# PR9025_A.net
KiCad netlist of a schematic drawn in EAGLE
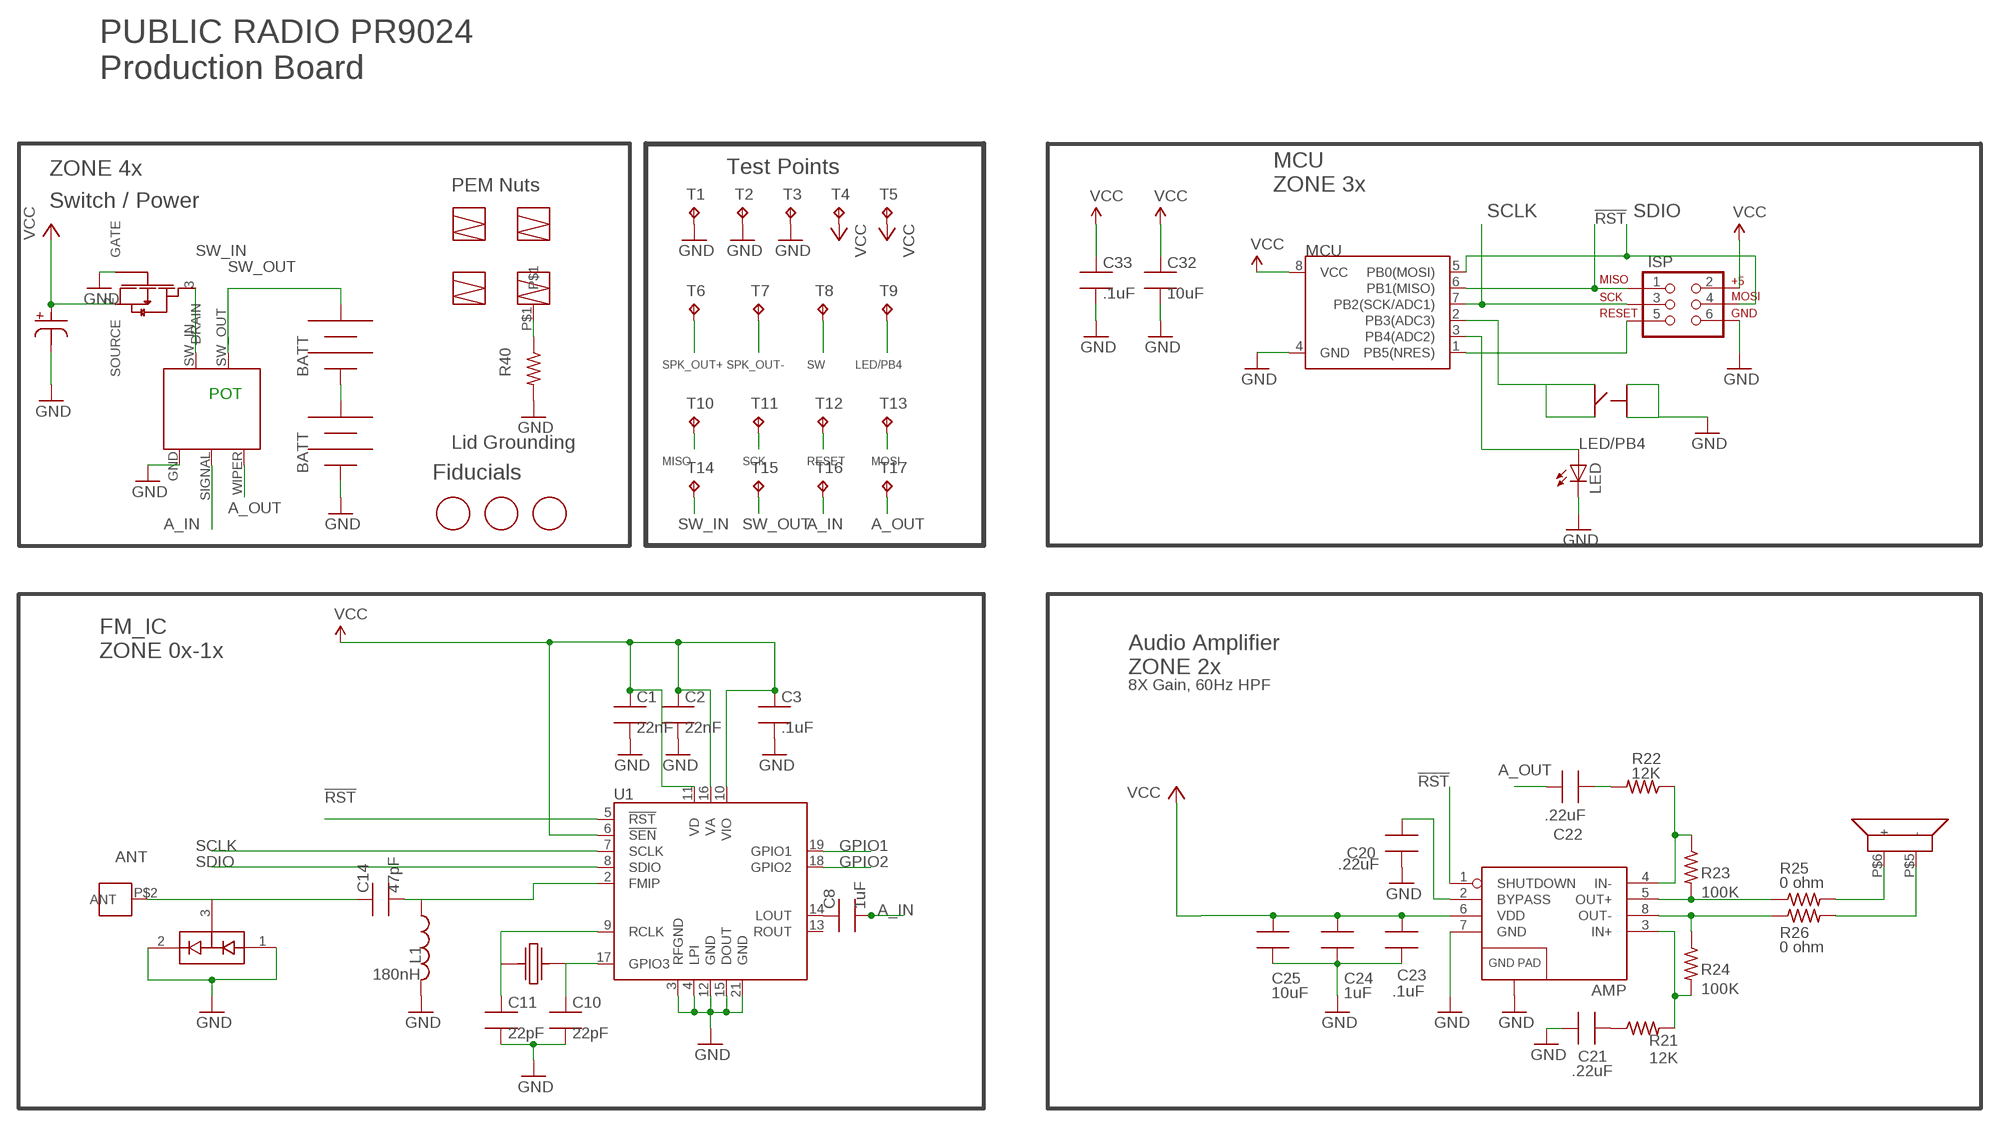
[diagram p0: schematic, sheet 1]

(export (version "E")
  (design (tool "Eeschema 10.0.6"))
  (components
    (comp (ref "AMP")
      (value "TPA6203A1")
      (footprint "eagle-import:8-MSOP")
      (libsource (lib "eagle-import") (part "TPA6203A1"))
    )
    (comp (ref "ANT_MOUNT")
      (value "DNP")
      (footprint "eagle-import:PEM_M3")
      (libsource (lib "eagle-import") (part "M3_PEMNUT"))
    )
    (comp (ref "C1")
      (value "22nF")
      (footprint "eagle-import:0603_CPL")
      (fields
        (field (name "MFG_PN") "CL10B223KB8NNNC")
        (field (name "TOL") "10%")
        (field (name "VOLTAGE") "16V")
      )
      (libsource (lib "eagle-import") (part "C_SMT_0603_CPL"))
    )
    (comp (ref "C2")
      (value "22nF")
      (footprint "eagle-import:0603_CPL")
      (fields
        (field (name "MFG_PN") "CL10B223KB8NNNC")
        (field (name "TOL") "10%")
        (field (name "VOLTAGE") "16V")
      )
      (libsource (lib "eagle-import") (part "C_SMT_0603_CPL"))
    )
    (comp (ref "C3")
      (value ".1uF")
      (footprint "eagle-import:0603_CPL")
      (fields
        (field (name "MFG_PN") "CL10B104KB8SFNC")
        (field (name "TOL") "10%")
        (field (name "VOLTAGE") "16V")
      )
      (libsource (lib "eagle-import") (part "C_SMT_0603_CPL"))
    )
    (comp (ref "C8")
      (value "1uF")
      (footprint "eagle-import:0603_CPL")
      (fields
        (field (name "MFG_PN") "CL10B105KP8NNNC")
        (field (name "TOL") "10%")
        (field (name "VOLTAGE") "10V")
      )
      (libsource (lib "eagle-import") (part "C_SMT_0603_CPL"))
    )
    (comp (ref "C10")
      (value "22pF")
      (footprint "eagle-import:0603_CPL")
      (fields
        (field (name "MFG_PN") "C1608C0G1H220J080AA")
        (field (name "TOL") "5%")
        (field (name "VOLTAGE") "50V")
      )
      (libsource (lib "eagle-import") (part "C_SMT_0603_CPL"))
    )
    (comp (ref "C11")
      (value "22pF")
      (footprint "eagle-import:0603_CPL")
      (fields
        (field (name "MFG_PN") "C1608C0G1H220J080AA")
        (field (name "TOL") "5%")
        (field (name "VOLTAGE") "50V")
      )
      (libsource (lib "eagle-import") (part "C_SMT_0603_CPL"))
    )
    (comp (ref "C14")
      (value "47pF")
      (footprint "eagle-import:0603_CPL")
      (fields
        (field (name "MFG_PN") "CL10C470JB8NCNC")
        (field (name "TOL") "5%")
        (field (name "VOLTAGE") "50V")
      )
      (libsource (lib "eagle-import") (part "C_SMT_0603_CPL"))
    )
    (comp (ref "C20")
      (value ".22uF")
      (footprint "eagle-import:0603_CPL")
      (fields
        (field (name "MFG_PN") "C1608X7R1C224K080AC")
        (field (name "TOL") "10%")
        (field (name "VOLTAGE") "16V")
      )
      (libsource (lib "eagle-import") (part "C_SMT_0603_CPL"))
    )
    (comp (ref "C21")
      (value ".22uF")
      (footprint "eagle-import:0603_CPL")
      (fields
        (field (name "MFG_PN") "C1608X7R1C224K080AC")
        (field (name "TOL") "10%")
        (field (name "VOLTAGE") "16V")
      )
      (libsource (lib "eagle-import") (part "C_SMT_0603_CPL"))
    )
    (comp (ref "C22")
      (value ".22uF")
      (footprint "eagle-import:0603_CPL")
      (fields
        (field (name "MFG_PN") "C1608X7R1C224K080AC")
        (field (name "TOL") "10%")
        (field (name "VOLTAGE") "16V")
      )
      (libsource (lib "eagle-import") (part "C_SMT_0603_CPL"))
    )
    (comp (ref "C23")
      (value ".1uF")
      (footprint "eagle-import:0603_CPL")
      (fields
        (field (name "MFG_PN") "CL10B104KB8SFNC")
        (field (name "TOL") "10%")
        (field (name "VOLTAGE") "16V")
      )
      (libsource (lib "eagle-import") (part "C_SMT_0603_CPL"))
    )
    (comp (ref "C24")
      (value "1uF")
      (footprint "eagle-import:0603_CPL")
      (fields
        (field (name "MFG_PN") "CL10B105KP8NNNC")
        (field (name "TOL") "10%")
        (field (name "VOLTAGE") "10V")
      )
      (libsource (lib "eagle-import") (part "C_SMT_0603_CPL"))
    )
    (comp (ref "C25")
      (value "10uF")
      (footprint "eagle-import:0603_CPL")
      (fields
        (field (name "MFG_PN") "CL10A106MQ8NNNC")
        (field (name "TOL") "20%")
        (field (name "VOLTAGE") "6.3V")
      )
      (libsource (lib "eagle-import") (part "C_SMT_0603_CPL"))
    )
    (comp (ref "C32")
      (value "10uF")
      (footprint "eagle-import:0603_CPL")
      (fields
        (field (name "MFG_PN") "CL10A106MQ8NNNC")
        (field (name "TOL") "20%")
        (field (name "VOLTAGE") "6.3V")
      )
      (libsource (lib "eagle-import") (part "C_SMT_0603_CPL"))
    )
    (comp (ref "C33")
      (value ".1uF")
      (footprint "eagle-import:0603_CPL")
      (fields
        (field (name "MFG_PN") "CL10B104KB8SFNC")
        (field (name "TOL") "10%")
        (field (name "VOLTAGE") "16V")
      )
      (libsource (lib "eagle-import") (part "C_SMT_0603_CPL"))
    )
    (comp (ref "C40")
      (value "220uF")
      (footprint "eagle-import:NICHICON_UD_63")
      (fields (field (name "TOL") "20%") (field (name "VOLTAGE") "16V"))
      (libsource (lib "eagle-import") (part "NICHICON_SERIESUD"))
    )
    (comp (ref "D1")
      (value "BAV99")
      (footprint "eagle-import:SOT23_CPL")
      (fields (field (name "MFG_PN") "BAV99,215"))
      (libsource (lib "eagle-import") (part "BAV99"))
    )
    (comp (ref "FET1")
      (value "AO3435")
      (footprint "eagle-import:SOT23_CPL")
      (fields (field (name "MFG_PN") "AO3435"))
      (libsource (lib "eagle-import") (part "AO3435"))
    )
    (comp (ref "ISP")
      (value "AVR_SPI_PRG_6NS")
      (footprint "eagle-import:2X3-NS")
      (libsource (lib "eagle-import") (part "AVR_SPI_PRG_6NS"))
    )
    (comp (ref "JP5")
      (value "BK-92_MPD_AA_BATT_CLIP")
      (footprint "eagle-import:BK92_AA_BATT")
      (fields (field (name "MFG_PN") "2 of BK92 - supplied by CL Labs"))
      (libsource (lib "eagle-import") (part "BK-92_MPD_AA_BATT_CLIP"))
    )
    (comp (ref "JP6")
      (value "BK-92_MPD_AA_BATT_CLIP")
      (footprint "eagle-import:BK92_AA_BATT")
      (fields (field (name "MFG_PN") "2 of BK92 - supplied by CL Labs"))
      (libsource (lib "eagle-import") (part "BK-92_MPD_AA_BATT_CLIP"))
    )
    (comp (ref "L1")
      (value "180nH")
      (footprint "eagle-import:0805_ADAFRUIT")
      (fields
        (field (name "CURRENT") "400mA")
        (field (name "DCR") "640m")
        (field (name "MFG_PN") "AISC-0805-R18J-T")
        (field (name "TOL") "5%")
      )
      (libsource (lib "eagle-import") (part "L_SMT_0805_ADAFRUIT"))
    )
    (comp (ref "LED")
      (value "HSMC-C265_REVERSE_MOUNT_LED")
      (footprint "eagle-import:HSMC-C265_REVERSE_MOUN_LED")
      (libsource (lib "eagle-import") (part "HSMC-C265_REVERSE_MOUNT_LED"))
    )
    (comp (ref "MARK1")
      (value "FIDUCIAL")
      (footprint "eagle-import:FIDUCIAL_1MM")
      (libsource (lib "eagle-import") (part "FIDUCIAL"))
    )
    (comp (ref "MARK2")
      (value "FIDUCIAL")
      (footprint "eagle-import:FIDUCIAL_1MM")
      (libsource (lib "eagle-import") (part "FIDUCIAL"))
    )
    (comp (ref "MARK3")
      (value "FIDUCIAL")
      (footprint "eagle-import:FIDUCIAL_1MM")
      (libsource (lib "eagle-import") (part "FIDUCIAL"))
    )
    (comp (ref "MCU")
      (value "ATTINY45TINY45-20-SMT")
      (footprint "eagle-import:8-SOIC")
      (libsource (lib "eagle-import") (part "ATTINY45TINY45-20-SMT"))
    )
    (comp (ref "R1")
      (value "VOLUME_POT")
      (footprint "eagle-import:H17112NS_A10K_L20F-002")
      (libsource (lib "eagle-import") (part "VOLUME_POT"))
    )
    (comp (ref "R21")
      (value "12K")
      (footprint "eagle-import:0603_CPL")
      (fields
        (field (name "MFG_PN") "RC0603FR-0712KL")
        (field (name "POWER") "1/10W")
        (field (name "TOL") "1%")
      )
      (libsource (lib "eagle-import") (part "R_SMT_R0603_CPL"))
    )
    (comp (ref "R22")
      (value "12K")
      (footprint "eagle-import:0603_CPL")
      (fields
        (field (name "MFG_PN") "RC0603FR-0712KL")
        (field (name "POWER") "1/10W")
        (field (name "TOL") "1%")
      )
      (libsource (lib "eagle-import") (part "R_SMT_R0603_CPL"))
    )
    (comp (ref "R23")
      (value "100K")
      (footprint "eagle-import:0603_CPL")
      (fields
        (field (name "MFG_PN") "ERJ-3EKF1003V")
        (field (name "POWER") "1/10W")
        (field (name "TOL") "1%")
      )
      (libsource (lib "eagle-import") (part "R_SMT_R0603_CPL"))
    )
    (comp (ref "R24")
      (value "100K")
      (footprint "eagle-import:0603_CPL")
      (fields
        (field (name "MFG_PN") "ERJ-3EKF1003V")
        (field (name "POWER") "1/10W")
        (field (name "TOL") "1%")
      )
      (libsource (lib "eagle-import") (part "R_SMT_R0603_CPL"))
    )
    (comp (ref "R25")
      (value "0 ohm")
      (footprint "eagle-import:0805_ADAFRUIT")
      (fields (field (name "MFG_PN") "ERJ-6GEY0R00V "))
      (libsource (lib "eagle-import") (part "R_SMT_0805_ADAFRUIT"))
    )
    (comp (ref "R26")
      (value "0 ohm")
      (footprint "eagle-import:0805_ADAFRUIT")
      (fields (field (name "MFG_PN") "ERJ-6GEY0R00V "))
      (libsource (lib "eagle-import") (part "R_SMT_0805_ADAFRUIT"))
    )
    (comp (ref "R40")
      (value "DNP")
      (footprint "eagle-import:0603_CPL")
      (fields (field (name "MFG_PN") "ERJ-3GEY0R00V"))
      (libsource (lib "eagle-import") (part "R_SMT_R0603_CPL"))
    )
    (comp (ref "SPKR_PLACE")
      (value "DNP")
      (footprint "eagle-import:PR2024_SPKR_PLACE(SMD)")
      (libsource (lib "eagle-import") (part "PR2024_SPKR_SMD"))
    )
    (comp (ref "SW1")
      (value "C&K_PTS645")
      (footprint "eagle-import:C&K_PTS645_SMT")
      (libsource (lib "eagle-import") (part "C&K_PTS645"))
    )
    (comp (ref "T1")
      (value "TPTP20R")
      (footprint "eagle-import:TP20R")
      (libsource (lib "eagle-import") (part "TPTP20R"))
    )
    (comp (ref "T2")
      (value "TPTP20R")
      (footprint "eagle-import:TP20R")
      (libsource (lib "eagle-import") (part "TPTP20R"))
    )
    (comp (ref "T3")
      (value "TPTP20R")
      (footprint "eagle-import:TP20R")
      (libsource (lib "eagle-import") (part "TPTP20R"))
    )
    (comp (ref "T4")
      (value "TPTP20R")
      (footprint "eagle-import:TP20R")
      (libsource (lib "eagle-import") (part "TPTP20R"))
    )
    (comp (ref "T5")
      (value "TPTP20R")
      (footprint "eagle-import:TP20R")
      (libsource (lib "eagle-import") (part "TPTP20R"))
    )
    (comp (ref "T6")
      (value "TPTP20R")
      (footprint "eagle-import:TP20R")
      (libsource (lib "eagle-import") (part "TPTP20R"))
    )
    (comp (ref "T7")
      (value "TPTP20R")
      (footprint "eagle-import:TP20R")
      (libsource (lib "eagle-import") (part "TPTP20R"))
    )
    (comp (ref "T8")
      (value "TPTP20R")
      (footprint "eagle-import:TP20R")
      (libsource (lib "eagle-import") (part "TPTP20R"))
    )
    (comp (ref "T9")
      (value "TPTP20R")
      (footprint "eagle-import:TP20R")
      (libsource (lib "eagle-import") (part "TPTP20R"))
    )
    (comp (ref "T10")
      (value "TPTP20R")
      (footprint "eagle-import:TP20R")
      (libsource (lib "eagle-import") (part "TPTP20R"))
    )
    (comp (ref "T11")
      (value "TPTP20R")
      (footprint "eagle-import:TP20R")
      (libsource (lib "eagle-import") (part "TPTP20R"))
    )
    (comp (ref "T12")
      (value "TPTP20R")
      (footprint "eagle-import:TP20R")
      (libsource (lib "eagle-import") (part "TPTP20R"))
    )
    (comp (ref "T13")
      (value "TPTP20R")
      (footprint "eagle-import:TP20R")
      (libsource (lib "eagle-import") (part "TPTP20R"))
    )
    (comp (ref "T14")
      (value "TPTP20R")
      (footprint "eagle-import:TP20R")
      (libsource (lib "eagle-import") (part "TPTP20R"))
    )
    (comp (ref "T15")
      (value "TPTP20R")
      (footprint "eagle-import:TP20R")
      (libsource (lib "eagle-import") (part "TPTP20R"))
    )
    (comp (ref "T16")
      (value "TPTP20R")
      (footprint "eagle-import:TP20R")
      (libsource (lib "eagle-import") (part "TPTP20R"))
    )
    (comp (ref "T17")
      (value "TPTP20R")
      (footprint "eagle-import:TP20R")
      (libsource (lib "eagle-import") (part "TPTP20R"))
    )
    (comp (ref "U$2")
      (value "PEM_SMT")
      (footprint "eagle-import:PEM_SMT")
      (libsource (lib "eagle-import") (part "PEM_SMT"))
    )
    (comp (ref "U$3")
      (value "PEM_SMT")
      (footprint "eagle-import:PEM_SMT")
      (libsource (lib "eagle-import") (part "PEM_SMT"))
    )
    (comp (ref "U$4")
      (value "PEM_SMT")
      (footprint "eagle-import:PEM_SMT")
      (libsource (lib "eagle-import") (part "PEM_SMT"))
    )
    (comp (ref "U$5")
      (value "PEM_M3_SMT_W/PIN")
      (footprint "eagle-import:PEM_SMT")
      (libsource (lib "eagle-import") (part "PEM_M3_SMT_W/PIN"))
    )
    (comp (ref "U1")
      (value "SI4702-C19-GMR")
      (footprint "eagle-import:SI470X_20_QFN")
      (fields (field (name "MFG_PN") "Si4702 C19 GM - supplied by CL Labs"))
      (libsource (lib "eagle-import") (part "SI4702-C19-GMR"))
    )
    (comp (ref "X1")
      (value "ABS25XTAL")
      (footprint "eagle-import:4-SOJ")
      (libsource (lib "eagle-import") (part "ABS25XTAL"))
    )
  )
  (nets
    (net (code "1") (name "/ANT") (class "Default")
      (node (ref "ANT_MOUNT") (pin "P$2") (pinfunction "ANT_P$2") (pintype "bidirectional"))
      (node (ref "C14") (pin "1") (pinfunction "1_1") (pintype "passive"))
      (node (ref "D1") (pin "3") (pinfunction "COM_3") (pintype "bidirectional"))
    )
    (net (code "2") (name "/A_IN") (class "Default")
      (node (ref "C8") (pin "2") (pinfunction "2_2") (pintype "passive"))
      (node (ref "R1") (pin "SIGNAL") (pinfunction "SIGNAL_SIGNAL") (pintype "bidirectional"))
      (node (ref "T16") (pin "TP") (pinfunction "TP_TP") (pintype "input"))
    )
    (net (code "3") (name "/A_OUT") (class "Default")
      (node (ref "C22") (pin "2") (pinfunction "2_2") (pintype "passive"))
      (node (ref "R1") (pin "WIPER") (pinfunction "WIPER_WIPER") (pintype "bidirectional"))
      (node (ref "T17") (pin "TP") (pinfunction "TP_TP") (pintype "input"))
    )
    (net (code "4") (name "/GPIO1") (class "Default")
      (node (ref "U1") (pin "19") (pinfunction "GPIO1_19") (pintype "bidirectional"))
    )
    (net (code "5") (name "/GPIO2") (class "Default")
      (node (ref "U1") (pin "18") (pinfunction "GPIO2_18") (pintype "bidirectional"))
    )
    (net (code "6") (name "/LED{slash}PB4") (class "Default")
      (node (ref "LED") (pin "P$1") (pinfunction "A_P$1") (pintype "passive"))
      (node (ref "MCU") (pin "3") (pinfunction "PB4(ADC2)_3") (pintype "bidirectional"))
      (node (ref "T9") (pin "TP") (pinfunction "TP_TP") (pintype "input"))
    )
    (net (code "7") (name "/RESET") (class "Default")
      (node (ref "ISP") (pin "5") (pinfunction "5_5") (pintype "passive"))
      (node (ref "MCU") (pin "1") (pinfunction "PB5(NRES)_1") (pintype "bidirectional"))
      (node (ref "T12") (pin "TP") (pinfunction "TP_TP") (pintype "input"))
    )
    (net (code "8") (name "/SCLK") (class "Default")
      (node (ref "ISP") (pin "3") (pinfunction "3_3") (pintype "passive"))
      (node (ref "MCU") (pin "7") (pinfunction "PB2(SCK/ADC1)_7") (pintype "bidirectional"))
      (node (ref "T11") (pin "TP") (pinfunction "TP_TP") (pintype "input"))
      (node (ref "U1") (pin "7") (pinfunction "SCLK_7") (pintype "bidirectional"))
    )
    (net (code "9") (name "/SDIO") (class "Default")
      (node (ref "ISP") (pin "4") (pinfunction "4_4") (pintype "passive"))
      (node (ref "MCU") (pin "5") (pinfunction "PB0(MOSI)_5") (pintype "bidirectional"))
      (node (ref "T13") (pin "TP") (pinfunction "TP_TP") (pintype "input"))
      (node (ref "U1") (pin "8") (pinfunction "SDIO_8") (pintype "bidirectional"))
    )
    (net (code "10") (name "/SPK_OUT+") (class "Default")
      (node (ref "R25") (pin "2") (pinfunction "2_2") (pintype "passive"))
      (node (ref "SPKR_PLACE") (pin "P$6") (pinfunction "+_P$6") (pintype "bidirectional"))
      (node (ref "T6") (pin "TP") (pinfunction "TP_TP") (pintype "input"))
    )
    (net (code "11") (name "/SPK_OUT-") (class "Default")
      (node (ref "R26") (pin "2") (pinfunction "2_2") (pintype "passive"))
      (node (ref "SPKR_PLACE") (pin "P$5") (pinfunction "-_P$5") (pintype "bidirectional"))
      (node (ref "T7") (pin "TP") (pinfunction "TP_TP") (pintype "input"))
    )
    (net (code "12") (name "/SW") (class "Default")
      (node (ref "MCU") (pin "2") (pinfunction "PB3(ADC3)_2") (pintype "bidirectional"))
      (node (ref "SW1") (pin "P$3") (pinfunction "P$3_P$3") (pintype "bidirectional"))
      (node (ref "SW1") (pin "P$4") (pinfunction "P$4_P$4") (pintype "bidirectional"))
      (node (ref "T8") (pin "TP") (pinfunction "TP_TP") (pintype "input"))
    )
    (net (code "13") (name "/SW_IN") (class "Default")
      (node (ref "FET1") (pin "3") (pinfunction "DRAIN_3") (pintype "bidirectional"))
      (node (ref "R1") (pin "SW_IN") (pinfunction "SW_IN_SW_IN") (pintype "bidirectional"))
      (node (ref "T14") (pin "TP") (pinfunction "TP_TP") (pintype "input"))
    )
    (net (code "14") (name "/SW_OUT") (class "Default")
      (node (ref "JP5") (pin "POS") (pinfunction "POS_POS") (pintype "bidirectional"))
      (node (ref "JP5") (pin "POS@2") (pinfunction "POS_POS@2") (pintype "bidirectional"))
      (node (ref "R1") (pin "SW_OUT") (pinfunction "SW_OUT_SW_OUT") (pintype "bidirectional"))
      (node (ref "T15") (pin "TP") (pinfunction "TP_TP") (pintype "input"))
    )
    (net (code "15") (name "/~{RST}") (class "Default")
      (node (ref "AMP") (pin "1") (pinfunction "SHUTDOWN_1") (pintype "input"))
      (node (ref "ISP") (pin "1") (pinfunction "1_1") (pintype "passive"))
      (node (ref "MCU") (pin "6") (pinfunction "PB1(MISO)_6") (pintype "bidirectional"))
      (node (ref "T10") (pin "TP") (pinfunction "TP_TP") (pintype "input"))
      (node (ref "U1") (pin "5") (pinfunction "~{RST}_5") (pintype "bidirectional"))
    )
    (net (code "16") (name "GND") (class "Default")
      (node (ref "AMP") (pin "7") (pinfunction "GND_7") (pintype "power_in"))
      (node (ref "AMP") (pin "9") (pinfunction "GND_9") (pintype "power_in"))
      (node (ref "C1") (pin "2") (pinfunction "2_2") (pintype "passive"))
      (node (ref "C10") (pin "2") (pinfunction "2_2") (pintype "passive"))
      (node (ref "C11") (pin "2") (pinfunction "2_2") (pintype "passive"))
      (node (ref "C2") (pin "2") (pinfunction "2_2") (pintype "passive"))
      (node (ref "C20") (pin "1") (pinfunction "1_1") (pintype "passive"))
      (node (ref "C21") (pin "1") (pinfunction "1_1") (pintype "passive"))
      (node (ref "C23") (pin "2") (pinfunction "2_2") (pintype "passive"))
      (node (ref "C24") (pin "2") (pinfunction "2_2") (pintype "passive"))
      (node (ref "C25") (pin "2") (pinfunction "2_2") (pintype "passive"))
      (node (ref "C3") (pin "2") (pinfunction "2_2") (pintype "passive"))
      (node (ref "C32") (pin "2") (pinfunction "2_2") (pintype "passive"))
      (node (ref "C33") (pin "2") (pinfunction "2_2") (pintype "passive"))
      (node (ref "C40") (pin "P$2") (pinfunction "P$2_P$2") (pintype "bidirectional"))
      (node (ref "D1") (pin "1") (pinfunction "A1_1") (pintype "bidirectional"))
      (node (ref "D1") (pin "2") (pinfunction "C2_2") (pintype "bidirectional"))
      (node (ref "FET1") (pin "1") (pinfunction "GATE_1") (pintype "bidirectional"))
      (node (ref "ISP") (pin "6") (pinfunction "6_6") (pintype "passive"))
      (node (ref "JP6") (pin "NEG") (pinfunction "NEG_NEG") (pintype "bidirectional"))
      (node (ref "JP6") (pin "NEG@2") (pinfunction "NEG_NEG@2") (pintype "bidirectional"))
      (node (ref "L1") (pin "2") (pinfunction "2_2") (pintype "passive"))
      (node (ref "LED") (pin "P$2") (pinfunction "C_P$2") (pintype "passive"))
      (node (ref "MCU") (pin "4") (pinfunction "GND_4") (pintype "bidirectional"))
      (node (ref "R1") (pin "GND") (pinfunction "GND_GND") (pintype "bidirectional"))
      (node (ref "R40") (pin "2") (pinfunction "2_2") (pintype "passive"))
      (node (ref "SW1") (pin "P$1") (pinfunction "P$1_P$1") (pintype "bidirectional"))
      (node (ref "SW1") (pin "P$2") (pinfunction "P$2_P$2") (pintype "bidirectional"))
      (node (ref "T1") (pin "TP") (pinfunction "TP_TP") (pintype "input"))
      (node (ref "T2") (pin "TP") (pinfunction "TP_TP") (pintype "input"))
      (node (ref "T3") (pin "TP") (pinfunction "TP_TP") (pintype "input"))
      (node (ref "U1") (pin "12") (pinfunction "GND_12") (pintype "bidirectional"))
      (node (ref "U1") (pin "15") (pinfunction "DOUT_15") (pintype "bidirectional"))
      (node (ref "U1") (pin "21") (pinfunction "GND_21") (pintype "bidirectional"))
      (node (ref "U1") (pin "3") (pinfunction "RFGND_3") (pintype "bidirectional"))
      (node (ref "U1") (pin "4") (pinfunction "LPI_4") (pintype "bidirectional"))
    )
    (net (code "17") (name "Net-(AMP-BYPASS)") (class "Default")
      (node (ref "AMP") (pin "2") (pinfunction "BYPASS_2") (pintype "bidirectional"))
      (node (ref "C20") (pin "2") (pinfunction "2_2") (pintype "passive"))
    )
    (net (code "18") (name "Net-(AMP-IN+)") (class "Default")
      (node (ref "AMP") (pin "3") (pinfunction "IN+_3") (pintype "bidirectional"))
      (node (ref "R21") (pin "2") (pinfunction "2_2") (pintype "passive"))
      (node (ref "R24") (pin "2") (pinfunction "2_2") (pintype "passive"))
    )
    (net (code "19") (name "Net-(AMP-IN-)") (class "Default")
      (node (ref "AMP") (pin "4") (pinfunction "IN-_4") (pintype "bidirectional"))
      (node (ref "R22") (pin "1") (pinfunction "1_1") (pintype "passive"))
      (node (ref "R23") (pin "1") (pinfunction "1_1") (pintype "passive"))
    )
    (net (code "20") (name "Net-(AMP-OUT+)") (class "Default")
      (node (ref "AMP") (pin "5") (pinfunction "OUT+_5") (pintype "bidirectional"))
      (node (ref "R23") (pin "2") (pinfunction "2_2") (pintype "passive"))
      (node (ref "R25") (pin "1") (pinfunction "1_1") (pintype "passive"))
    )
    (net (code "21") (name "Net-(AMP-OUT-)") (class "Default")
      (node (ref "AMP") (pin "8") (pinfunction "OUT-_8") (pintype "bidirectional"))
      (node (ref "R24") (pin "1") (pinfunction "1_1") (pintype "passive"))
      (node (ref "R26") (pin "1") (pinfunction "1_1") (pintype "passive"))
    )
    (net (code "22") (name "Net-(C21-Pad2)") (class "Default")
      (node (ref "C21") (pin "2") (pinfunction "2_2") (pintype "passive"))
      (node (ref "R21") (pin "1") (pinfunction "1_1") (pintype "passive"))
    )
    (net (code "23") (name "Net-(C22-Pad1)") (class "Default")
      (node (ref "C22") (pin "1") (pinfunction "1_1") (pintype "passive"))
      (node (ref "R22") (pin "2") (pinfunction "2_2") (pintype "passive"))
    )
    (net (code "24") (name "Net-(JP5-NEG-PadNEG@2)") (class "Default")
      (node (ref "JP5") (pin "NEG") (pinfunction "NEG_NEG") (pintype "bidirectional"))
      (node (ref "JP5") (pin "NEG@2") (pinfunction "NEG_NEG@2") (pintype "bidirectional"))
      (node (ref "JP6") (pin "POS") (pinfunction "POS_POS") (pintype "bidirectional"))
      (node (ref "JP6") (pin "POS@2") (pinfunction "POS_POS@2") (pintype "bidirectional"))
    )
    (net (code "25") (name "Net-(R40-Pad1)") (class "Default")
      (node (ref "R40") (pin "1") (pinfunction "1_1") (pintype "passive"))
      (node (ref "U$5") (pin "P$1") (pinfunction "P$1_P$1") (pintype "bidirectional"))
    )
    (net (code "26") (name "Net-(U1-FMIP)") (class "Default")
      (node (ref "C14") (pin "2") (pinfunction "2_2") (pintype "passive"))
      (node (ref "L1") (pin "1") (pinfunction "1_1") (pintype "passive"))
      (node (ref "U1") (pin "2") (pinfunction "FMIP_2") (pintype "bidirectional"))
    )
    (net (code "27") (name "Net-(U1-GPIO3)") (class "Default")
      (node (ref "C10") (pin "1") (pinfunction "1_1") (pintype "passive"))
      (node (ref "U1") (pin "17") (pinfunction "GPIO3_17") (pintype "bidirectional"))
      (node (ref "X1") (pin "P$4") (pinfunction "P$4_P$4") (pintype "bidirectional"))
    )
    (net (code "28") (name "Net-(U1-LOUT)") (class "Default")
      (node (ref "C8") (pin "1") (pinfunction "1_1") (pintype "passive"))
      (node (ref "U1") (pin "14") (pinfunction "LOUT_14") (pintype "bidirectional"))
    )
    (net (code "29") (name "Net-(U1-RCLK)") (class "Default")
      (node (ref "C11") (pin "1") (pinfunction "1_1") (pintype "passive"))
      (node (ref "U1") (pin "9") (pinfunction "RCLK_9") (pintype "bidirectional"))
      (node (ref "X1") (pin "P$1") (pinfunction "P$1_P$1") (pintype "bidirectional"))
    )
    (net (code "30") (name "VCC") (class "Default")
      (node (ref "AMP") (pin "6") (pinfunction "VDD_6") (pintype "power_in"))
      (node (ref "C1") (pin "1") (pinfunction "1_1") (pintype "passive"))
      (node (ref "C2") (pin "1") (pinfunction "1_1") (pintype "passive"))
      (node (ref "C23") (pin "1") (pinfunction "1_1") (pintype "passive"))
      (node (ref "C24") (pin "1") (pinfunction "1_1") (pintype "passive"))
      (node (ref "C25") (pin "1") (pinfunction "1_1") (pintype "passive"))
      (node (ref "C3") (pin "1") (pinfunction "1_1") (pintype "passive"))
      (node (ref "C32") (pin "1") (pinfunction "1_1") (pintype "passive"))
      (node (ref "C33") (pin "1") (pinfunction "1_1") (pintype "passive"))
      (node (ref "C40") (pin "P$1") (pinfunction "P$1_P$1") (pintype "bidirectional"))
      (node (ref "FET1") (pin "2") (pinfunction "SOURCE_2") (pintype "bidirectional"))
      (node (ref "ISP") (pin "2") (pinfunction "2_2") (pintype "passive"))
      (node (ref "MCU") (pin "8") (pinfunction "VCC_8") (pintype "bidirectional"))
      (node (ref "T4") (pin "TP") (pinfunction "TP_TP") (pintype "input"))
      (node (ref "T5") (pin "TP") (pinfunction "TP_TP") (pintype "input"))
      (node (ref "U1") (pin "10") (pinfunction "VIO_10") (pintype "bidirectional"))
      (node (ref "U1") (pin "11") (pinfunction "VD_11") (pintype "bidirectional"))
      (node (ref "U1") (pin "16") (pinfunction "VA_16") (pintype "bidirectional"))
      (node (ref "U1") (pin "6") (pinfunction "~{SEN}_6") (pintype "bidirectional"))
    )
    (net (code "31") (name "unconnected-(U1-ROUT-Pad13)") (class "Default")
      (node (ref "U1") (pin "13") (pinfunction "ROUT_13") (pintype "bidirectional"))
    )
  )
)
